# CONNECTORS.net
KiCad netlist of a schematic drawn in Altium Designer
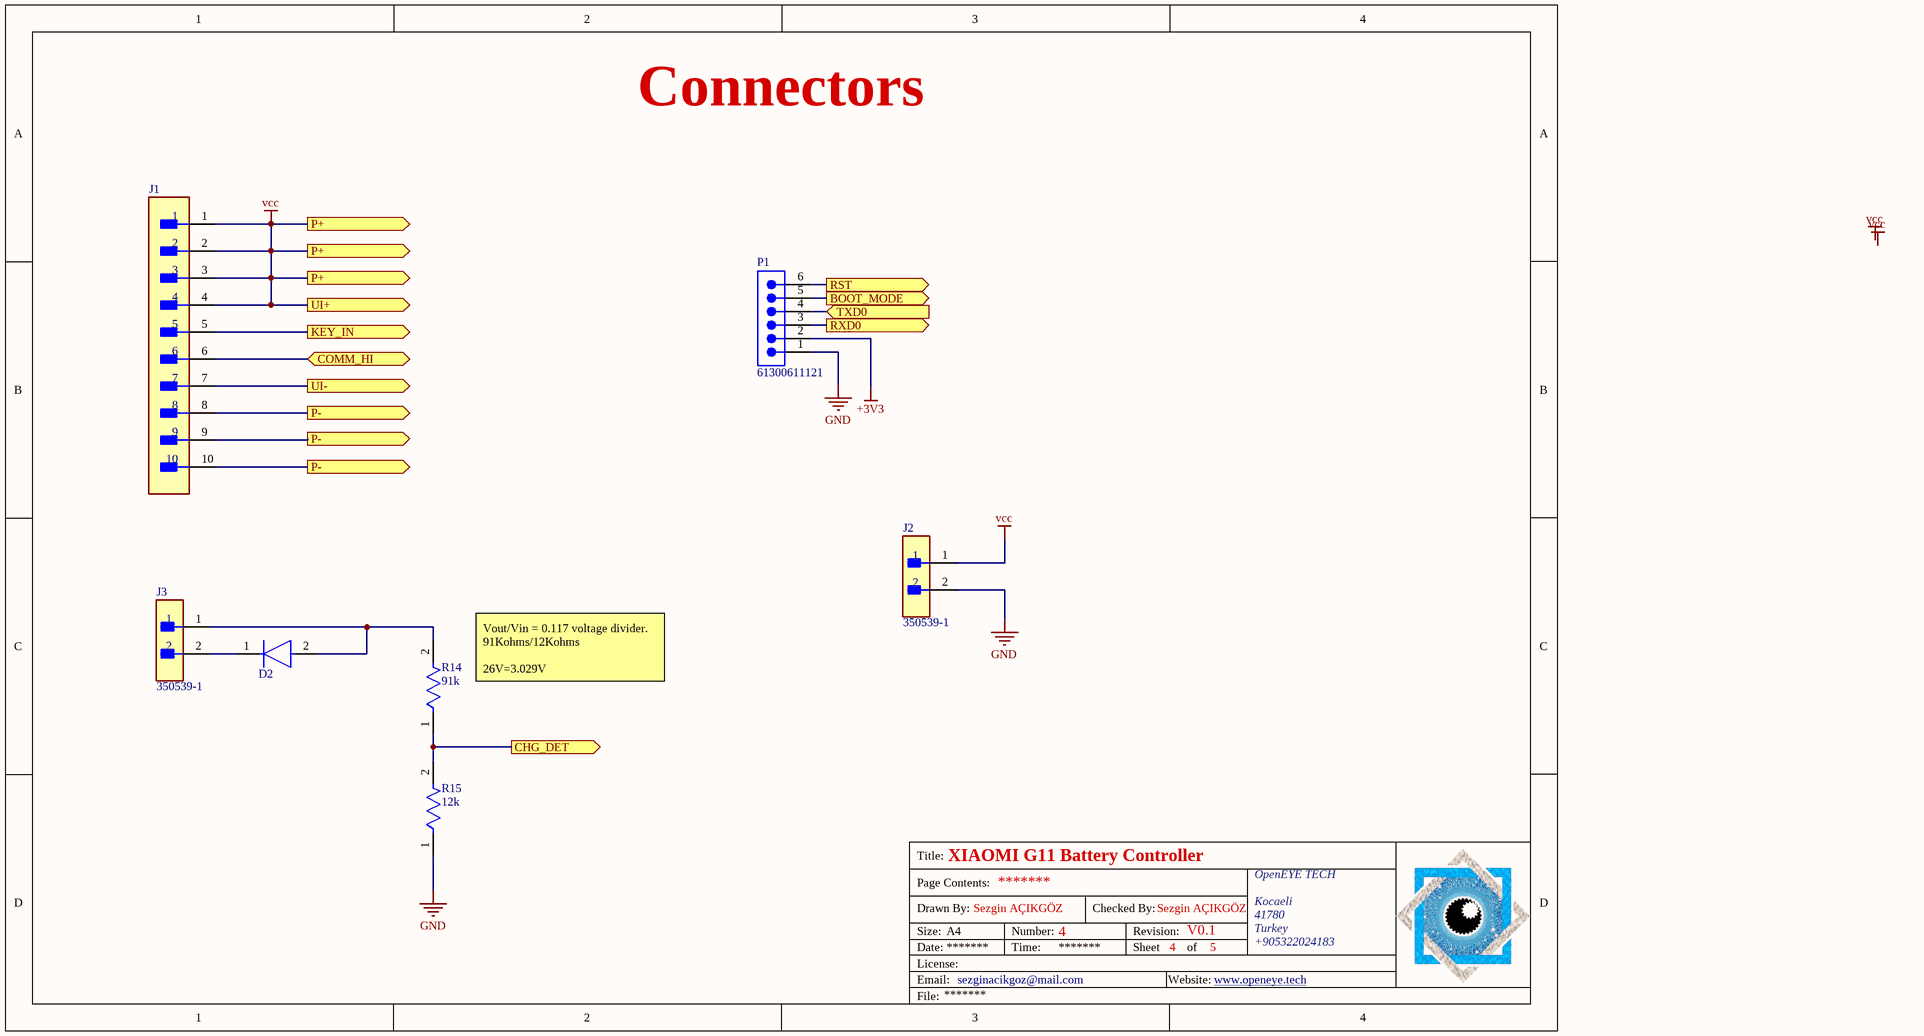
[diagram p0: CONNECTORS.SchDoc]

(export (version "E")
  (design (tool "Eeschema 10.0.6"))
  (components
    (comp (ref "D2")
      (value "ES2DA-13-F")
      (footprint "FP-SMA-MFG")
      (description "200V 2A Surface Mount Super-Fast Rectifier DO-214AC")
      (fields (field (name "MANUFACTURER") "Diodes Inc."))
      (libsource (lib "Altium Content Vault") (part "d7152d700b627762746794eb795d46e"))
    )
    (comp (ref "J1")
      (value "S10B-PH-K-S(LF)(SN)")
      (footprint "FP-S10B-PH-K-S_LF_SN-MFG")
      (description "CONN HEADER R/A 10POS 2MM")
      (libsource (lib "Altium Content Vault") (part "aee40dc8b284c03a16094555aa210be"))
    )
    (comp (ref "J2")
      (value "350539-1")
      (footprint "FP-350539-1-MFG")
      (description "CONN HEADER VERT 2POS 5.08MM")
      (fields
        (field (name "MANUFACTURER") "TE Connectivity")
        (field (name "OCTOPART") "https://octopart.com/350539-1-te+connectivity-46510628")
      )
      (libsource (lib "Altium Content Vault") (part "3bc925449376181038e59eaffc5286c"))
    )
    (comp (ref "J3")
      (value "350539-1")
      (footprint "FP-350539-1-MFG")
      (description "CONN HEADER VERT 2POS 5.08MM")
      (fields
        (field (name "MANUFACTURER") "TE Connectivity")
        (field (name "OCTOPART") "https://octopart.com/350539-1-te+connectivity-46510628")
      )
      (libsource (lib "Altium Content Vault") (part "3bc925449376181038e59eaffc5286c"))
    )
    (comp (ref "P1")
      (value "61300611121")
      (footprint "61300611121")
      (libsource (lib "Altium Content Vault") (part "Header_Male_1R_06P"))
    )
    (comp (ref "R14")
      (value "91k")
      (footprint "FP-RP731J-MFG")
      (fields
        (field (name "MANUFACTURER") "TE Connectivity")
        (field (name "OCTOPART") "https://octopart.com/rp73d1j8r45btdg-te+connectivity-42630912")
        (field (name "MANUFACTURER PART NUMBER") "RP73D1J8R45BTDG")
      )
      (libsource (lib "Altium Content Vault") (part "1029c3af85768c4190bb7ad29bc67b5"))
    )
    (comp (ref "R15")
      (value "12k")
      (footprint "FP-RP731J-MFG")
      (fields
        (field (name "MANUFACTURER") "TE Connectivity")
        (field (name "OCTOPART") "https://octopart.com/rp73d1j8r45btdg-te+connectivity-42630912")
        (field (name "MANUFACTURER PART NUMBER") "RP73D1J8R45BTDG")
      )
      (libsource (lib "Altium Content Vault") (part "1029c3af85768c4190bb7ad29bc67b5"))
    )
  )
  (nets
    (net (code "1") (name "+3V3") (class "Default")
      (node (ref "P1") (pin "2") (pinfunction "2_2") (pintype "passive"))
    )
    (net (code "2") (name "/BOOT_MODE") (class "Default")
      (node (ref "P1") (pin "5") (pinfunction "5_5") (pintype "passive"))
    )
    (net (code "3") (name "/CHG_DET") (class "Default")
      (node (ref "R14") (pin "1") (pinfunction "1_1") (pintype "passive"))
      (node (ref "R15") (pin "2") (pinfunction "2_2") (pintype "passive"))
    )
    (net (code "4") (name "/COMM_HI") (class "Default")
      (node (ref "J1") (pin "6") (pinfunction "6_6") (pintype "passive"))
    )
    (net (code "5") (name "/KEY_IN") (class "Default")
      (node (ref "J1") (pin "5") (pinfunction "5_5") (pintype "passive"))
    )
    (net (code "6") (name "/P-") (class "Default")
      (node (ref "J1") (pin "10") (pinfunction "10_10") (pintype "passive"))
      (node (ref "J1") (pin "8") (pinfunction "8_8") (pintype "passive"))
      (node (ref "J1") (pin "9") (pinfunction "9_9") (pintype "passive"))
    )
    (net (code "7") (name "/RST") (class "Default")
      (node (ref "P1") (pin "6") (pinfunction "6_6") (pintype "passive"))
    )
    (net (code "8") (name "/RXD0") (class "Default")
      (node (ref "P1") (pin "3") (pinfunction "3_3") (pintype "passive"))
    )
    (net (code "9") (name "/TXD0") (class "Default")
      (node (ref "P1") (pin "4") (pinfunction "4_4") (pintype "passive"))
    )
    (net (code "10") (name "/UI-") (class "Default")
      (node (ref "J1") (pin "7") (pinfunction "7_7") (pintype "passive"))
    )
    (net (code "11") (name "GND") (class "Default")
      (node (ref "J2") (pin "2") (pinfunction "2_2") (pintype "passive"))
      (node (ref "P1") (pin "1") (pinfunction "1_1") (pintype "passive"))
      (node (ref "R15") (pin "1") (pinfunction "1_1") (pintype "passive"))
    )
    (net (code "12") (name "Net-(D2-A)") (class "Default")
      (node (ref "D2") (pin "2") (pinfunction "A_2") (pintype "passive"))
      (node (ref "J3") (pin "1") (pinfunction "1_1") (pintype "passive"))
      (node (ref "R14") (pin "2") (pinfunction "2_2") (pintype "passive"))
    )
    (net (code "13") (name "Net-(D2-C)") (class "Default")
      (node (ref "D2") (pin "1") (pinfunction "C_1") (pintype "passive"))
      (node (ref "J3") (pin "2") (pinfunction "2_2") (pintype "passive"))
    )
    (net (code "14") (name "vcc") (class "Default")
      (node (ref "J1") (pin "1") (pinfunction "1_1") (pintype "passive"))
      (node (ref "J1") (pin "2") (pinfunction "2_2") (pintype "passive"))
      (node (ref "J1") (pin "3") (pinfunction "3_3") (pintype "passive"))
      (node (ref "J1") (pin "4") (pinfunction "4_4") (pintype "passive"))
      (node (ref "J2") (pin "1") (pinfunction "1_1") (pintype "passive"))
    )
  )
)
